# sc.net
KiCad netlist of a schematic drawn in EAGLE
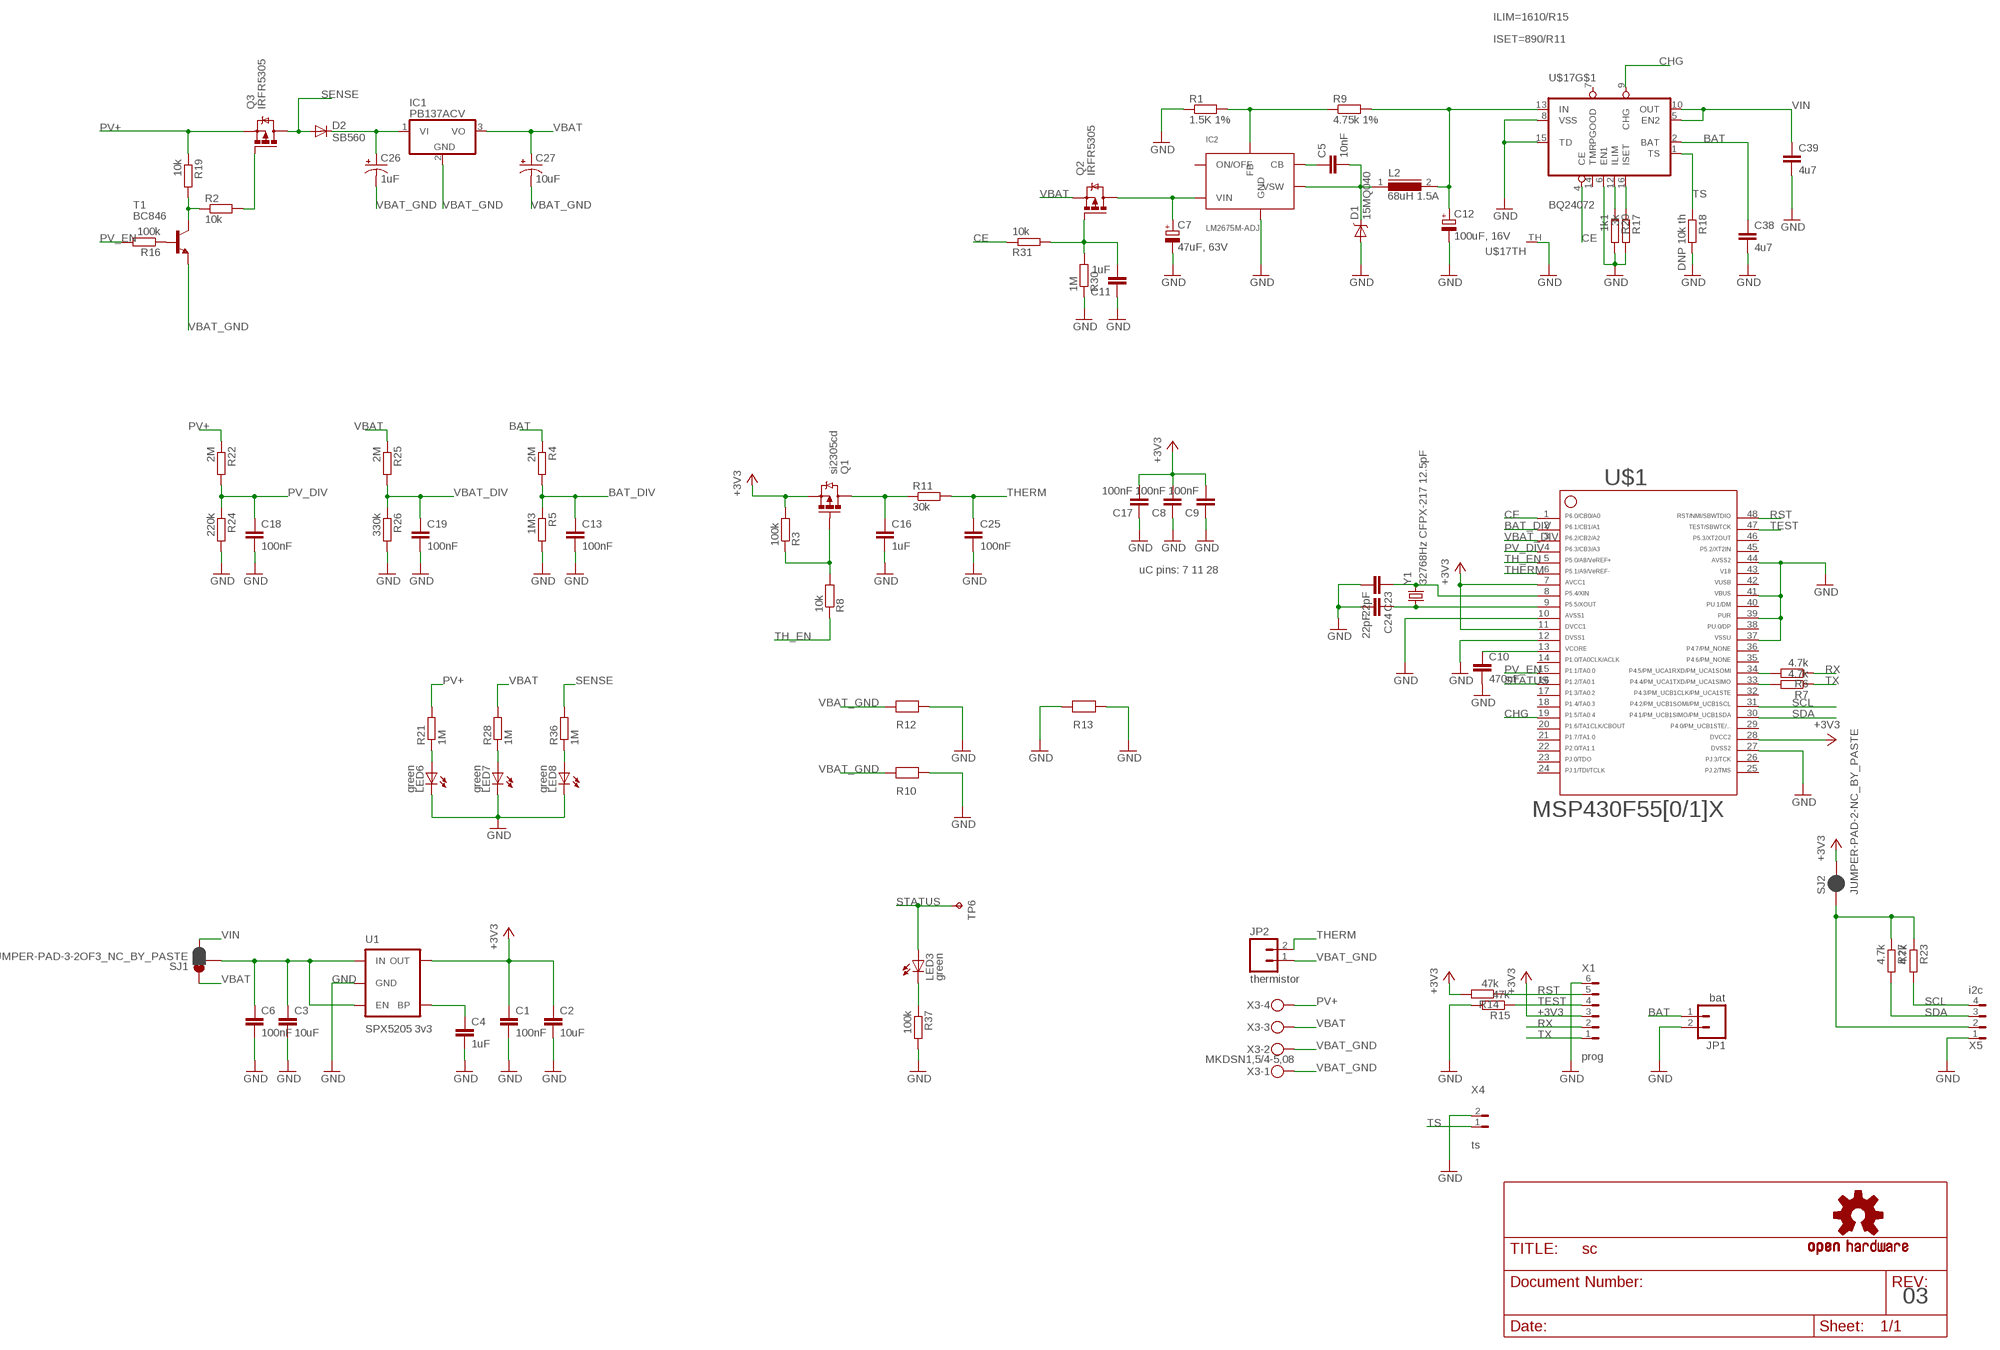
[diagram p0: schematic, sheet 1]

(export (version "E")
  (design (tool "Eeschema 10.0.6"))
  (components
    (comp (ref "C1")
      (value "100nF")
      (footprint "eagle-import:C0805")
      (libsource (lib "eagle-import") (part "C-EUC0805"))
    )
    (comp (ref "C2")
      (value "10uF")
      (footprint "eagle-import:C1206")
      (libsource (lib "eagle-import") (part "C-EUC1206"))
    )
    (comp (ref "C3")
      (value "10uF")
      (footprint "eagle-import:C1206")
      (libsource (lib "eagle-import") (part "C-EUC1206"))
    )
    (comp (ref "C4")
      (value "1uF")
      (footprint "eagle-import:C0805")
      (libsource (lib "eagle-import") (part "C-EUC0805"))
    )
    (comp (ref "C5")
      (value "10nF")
      (footprint "eagle-import:C0805")
      (libsource (lib "eagle-import") (part "C-EUC0805"))
    )
    (comp (ref "C6")
      (value "100nF")
      (footprint "eagle-import:C0805")
      (libsource (lib "eagle-import") (part "C-EUC0805"))
    )
    (comp (ref "C7")
      (value "47uF, 63V")
      (footprint "eagle-import:PANASONIC_F")
      (libsource (lib "eagle-import") (part "CPOL-EUF"))
    )
    (comp (ref "C8")
      (value "100nF")
      (footprint "eagle-import:C0805")
      (libsource (lib "eagle-import") (part "C-EUC0805"))
    )
    (comp (ref "C9")
      (value "100nF")
      (footprint "eagle-import:C0805")
      (libsource (lib "eagle-import") (part "C-EUC0805"))
    )
    (comp (ref "C10")
      (value "470nF")
      (footprint "eagle-import:C0805")
      (libsource (lib "eagle-import") (part "C-EUC0805"))
    )
    (comp (ref "C11")
      (value "1uF")
      (footprint "eagle-import:C0805")
      (libsource (lib "eagle-import") (part "C-EUC0805"))
    )
    (comp (ref "C12")
      (value "100uF, 16V")
      (footprint "eagle-import:PANASONIC_D")
      (libsource (lib "eagle-import") (part "CPOL-EUD"))
    )
    (comp (ref "C13")
      (value "100nF")
      (footprint "eagle-import:C0805")
      (libsource (lib "eagle-import") (part "C-EUC0805"))
    )
    (comp (ref "C16")
      (value "1uF")
      (footprint "eagle-import:C0805")
      (libsource (lib "eagle-import") (part "C-EUC0805"))
    )
    (comp (ref "C17")
      (value "100nF")
      (footprint "eagle-import:C0805")
      (libsource (lib "eagle-import") (part "C-EUC0805"))
    )
    (comp (ref "C18")
      (value "100nF")
      (footprint "eagle-import:C0805")
      (libsource (lib "eagle-import") (part "C-EUC0805"))
    )
    (comp (ref "C19")
      (value "100nF")
      (footprint "eagle-import:C0805")
      (libsource (lib "eagle-import") (part "C-EUC0805"))
    )
    (comp (ref "C23")
      (value "22pF")
      (footprint "eagle-import:C0805")
      (libsource (lib "eagle-import") (part "C-EUC0805"))
    )
    (comp (ref "C24")
      (value "22pF")
      (footprint "eagle-import:C0805")
      (libsource (lib "eagle-import") (part "C-EUC0805"))
    )
    (comp (ref "C25")
      (value "100nF")
      (footprint "eagle-import:C0805")
      (libsource (lib "eagle-import") (part "C-EUC0805"))
    )
    (comp (ref "C26")
      (value "1uF")
      (footprint "eagle-import:PANASONIC_D")
      (libsource (lib "eagle-import") (part "CAP_POLD"))
    )
    (comp (ref "C27")
      (value "10uF")
      (footprint "eagle-import:PANASONIC_D")
      (libsource (lib "eagle-import") (part "CAP_POLD"))
    )
    (comp (ref "C38")
      (value "4u7")
      (footprint "eagle-import:C1206")
      (libsource (lib "eagle-import") (part "C-EUC1206"))
    )
    (comp (ref "C39")
      (value "4u7")
      (footprint "eagle-import:C1206")
      (libsource (lib "eagle-import") (part "C-EUC1206"))
    )
    (comp (ref "D1")
      (value "15MQ040")
      (footprint "eagle-import:SMA-DIODE")
      (libsource (lib "eagle-import") (part "DIODE-SCHOTTKY-MBRA140"))
    )
    (comp (ref "D2")
      (value "SB560")
      (footprint "eagle-import:C1702-05")
      (libsource (lib "eagle-import") (part "DIODE-C1702-05"))
    )
    (comp (ref "IC1")
      (value "PB137ACV")
      (footprint "eagle-import:TO220V")
      (libsource (lib "eagle-import") (part "78TV12"))
    )
    (comp (ref "IC2")
      (value "LM2675M-ADJ")
      (footprint "eagle-import:SO-08")
      (libsource (lib "eagle-import") (part "LM2674"))
    )
    (comp (ref "JP1")
      (value "bat")
      (footprint "eagle-import:1X02")
      (libsource (lib "eagle-import") (part "M02PTH"))
    )
    (comp (ref "JP2")
      (value "thermistor")
      (footprint "eagle-import:1X02")
      (libsource (lib "eagle-import") (part "M02PTH"))
    )
    (comp (ref "L2")
      (value "68uH 1.5A")
      (footprint "eagle-import:DR125")
      (libsource (lib "eagle-import") (part "DR125"))
    )
    (comp (ref "LED3")
      (value "green")
      (footprint "eagle-import:CHIPLED_0805")
      (libsource (lib "eagle-import") (part "LEDCHIPLED_0805"))
    )
    (comp (ref "LED6")
      (value "green")
      (footprint "eagle-import:CHIP-LED0805")
      (libsource (lib "eagle-import") (part "LEDCHIP-LED0805"))
    )
    (comp (ref "LED7")
      (value "green")
      (footprint "eagle-import:CHIP-LED0805")
      (libsource (lib "eagle-import") (part "LEDCHIP-LED0805"))
    )
    (comp (ref "LED8")
      (value "green")
      (footprint "eagle-import:CHIP-LED0805")
      (libsource (lib "eagle-import") (part "LEDCHIP-LED0805"))
    )
    (comp (ref "Q1")
      (value "si2305cd")
      (footprint "eagle-import:SOT23-3_POWER@1")
      (libsource (lib "eagle-import") (part "MOSFET-PCHANNELSMD_POWER"))
    )
    (comp (ref "Q2")
      (value "IRFR5305")
      (footprint "eagle-import:D-PAK_TO252AA")
      (libsource (lib "eagle-import") (part "IRF?5305R"))
    )
    (comp (ref "Q3")
      (value "IRFR5305")
      (footprint "eagle-import:D-PAK_TO252AA")
      (libsource (lib "eagle-import") (part "IRF?5305R"))
    )
    (comp (ref "R1")
      (value "1.5K 1%")
      (footprint "eagle-import:R0805W")
      (libsource (lib "eagle-import") (part "R-EU_R0805W"))
    )
    (comp (ref "R2")
      (value "10k")
      (footprint "eagle-import:R0805W")
      (libsource (lib "eagle-import") (part "R-EU_R0805W"))
    )
    (comp (ref "R3")
      (value "100k")
      (footprint "eagle-import:R0805W")
      (libsource (lib "eagle-import") (part "R-EU_R0805W"))
    )
    (comp (ref "R4")
      (value "2M")
      (footprint "eagle-import:R0805W")
      (libsource (lib "eagle-import") (part "R-EU_R0805W"))
    )
    (comp (ref "R5")
      (value "1M3")
      (footprint "eagle-import:R0805W")
      (libsource (lib "eagle-import") (part "R-EU_R0805W"))
    )
    (comp (ref "R6")
      (value "4.7k")
      (footprint "eagle-import:R0805W")
      (libsource (lib "eagle-import") (part "R-EU_R0805W"))
    )
    (comp (ref "R7")
      (value "4.7k")
      (footprint "eagle-import:R0805W")
      (libsource (lib "eagle-import") (part "R-EU_R0805W"))
    )
    (comp (ref "R8")
      (value "10k")
      (footprint "eagle-import:R0805W")
      (libsource (lib "eagle-import") (part "R-EU_R0805W"))
    )
    (comp (ref "R9")
      (value "4.75k 1%")
      (footprint "eagle-import:R0805W")
      (libsource (lib "eagle-import") (part "R-EU_R0805W"))
    )
    (comp (ref "R10")
      (value "0R_0805")
      (footprint "eagle-import:R0805W")
      (libsource (lib "eagle-import") (part "0R_0805"))
    )
    (comp (ref "R11")
      (value "30k")
      (footprint "eagle-import:R0805W")
      (libsource (lib "eagle-import") (part "R-EU_R0805W"))
    )
    (comp (ref "R12")
      (value "0R_0805")
      (footprint "eagle-import:R0805W")
      (libsource (lib "eagle-import") (part "0R_0805"))
    )
    (comp (ref "R13")
      (value "0R_0805")
      (footprint "eagle-import:R0805W")
      (libsource (lib "eagle-import") (part "0R_0805"))
    )
    (comp (ref "R14")
      (value "47k")
      (footprint "eagle-import:R0805W")
      (libsource (lib "eagle-import") (part "R-EU_R0805W"))
    )
    (comp (ref "R15")
      (value "47k")
      (footprint "eagle-import:R0805W")
      (libsource (lib "eagle-import") (part "R-EU_R0805W"))
    )
    (comp (ref "R16")
      (value "100k")
      (footprint "eagle-import:R0805W")
      (libsource (lib "eagle-import") (part "R-EU_R0805W"))
    )
    (comp (ref "R17")
      (value "3k")
      (footprint "eagle-import:R0805W")
      (libsource (lib "eagle-import") (part "R-EU_R0805W"))
    )
    (comp (ref "R18")
      (value "DNP 10k th")
      (footprint "eagle-import:R0805W")
      (libsource (lib "eagle-import") (part "R-EU_R0805W"))
    )
    (comp (ref "R19")
      (value "10k")
      (footprint "eagle-import:R0805W")
      (libsource (lib "eagle-import") (part "R-EU_R0805W"))
    )
    (comp (ref "R20")
      (value "1k1")
      (footprint "eagle-import:R0805W")
      (libsource (lib "eagle-import") (part "R-EU_R0805W"))
    )
    (comp (ref "R21")
      (value "1M")
      (footprint "eagle-import:R0805W")
      (libsource (lib "eagle-import") (part "R-EU_R0805W"))
    )
    (comp (ref "R22")
      (value "2M")
      (footprint "eagle-import:R0805W")
      (libsource (lib "eagle-import") (part "R-EU_R0805W"))
    )
    (comp (ref "R23")
      (value "4.7k")
      (footprint "eagle-import:R0805W")
      (libsource (lib "eagle-import") (part "R-EU_R0805W"))
    )
    (comp (ref "R24")
      (value "220k")
      (footprint "eagle-import:R0805W")
      (libsource (lib "eagle-import") (part "R-EU_R0805W"))
    )
    (comp (ref "R25")
      (value "2M")
      (footprint "eagle-import:R0805W")
      (libsource (lib "eagle-import") (part "R-EU_R0805W"))
    )
    (comp (ref "R26")
      (value "330k")
      (footprint "eagle-import:R0805W")
      (libsource (lib "eagle-import") (part "R-EU_R0805W"))
    )
    (comp (ref "R27")
      (value "4.7k")
      (footprint "eagle-import:R0805W")
      (libsource (lib "eagle-import") (part "R-EU_R0805W"))
    )
    (comp (ref "R28")
      (value "1M")
      (footprint "eagle-import:R0805W")
      (libsource (lib "eagle-import") (part "R-EU_R0805W"))
    )
    (comp (ref "R30")
      (value "1M")
      (footprint "eagle-import:R0805W")
      (libsource (lib "eagle-import") (part "R-EU_R0805W"))
    )
    (comp (ref "R31")
      (value "10k")
      (footprint "eagle-import:R0805W")
      (libsource (lib "eagle-import") (part "R-EU_R0805W"))
    )
    (comp (ref "R36")
      (value "1M")
      (footprint "eagle-import:R0805W")
      (libsource (lib "eagle-import") (part "R-EU_R0805W"))
    )
    (comp (ref "R37")
      (value "100k")
      (footprint "eagle-import:R0805W")
      (libsource (lib "eagle-import") (part "R-EU_R0805W"))
    )
    (comp (ref "SJ1")
      (value "JUMPER-PAD-3-2OF3_NC_BY_PASTE")
      (footprint "eagle-import:PAD-JUMPER-3-2OF3_NC_BY_PASTE_YES_SILK_FULL_BOX")
      (libsource (lib "eagle-import") (part "JUMPER-PAD-3-2OF3_NC_BY_PASTE"))
    )
    (comp (ref "SJ2")
      (value "JUMPER-PAD-2-NC_BY_PASTE")
      (footprint "eagle-import:PAD-JUMPER-2-NC_BY_PASTE_YES_SILK")
      (libsource (lib "eagle-import") (part "JUMPER-PAD-2-NC_BY_PASTE"))
    )
    (comp (ref "T1")
      (value "BC846")
      (footprint "eagle-import:SOT23")
      (libsource (lib "eagle-import") (part "BC846"))
    )
    (comp (ref "TP6")
      (value "TPTP12R")
      (footprint "eagle-import:TP12R")
      (libsource (lib "eagle-import") (part "TPTP12R"))
    )
    (comp (ref "U$1")
      (value "F55[0/1]X---PT48")
      (footprint "eagle-import:PT48")
      (libsource (lib "eagle-import") (part "F55[0/1]X---PT48"))
    )
    (comp (ref "U$7")
      (value "OSHW-LOGOM")
      (footprint "eagle-import:OSHW-LOGO-M")
      (libsource (lib "eagle-import") (part "OSHW-LOGOM"))
    )
    (comp (ref "U$17")
      (value "BQ24072")
      (footprint "eagle-import:S-PVQFN-N16")
      (libsource (lib "eagle-import") (part "BQ24072"))
    )
    (comp (ref "U1")
      (value "SPX5205 3v3")
      (footprint "eagle-import:SOT23-5")
      (libsource (lib "eagle-import") (part "V_REG_LDOSMD"))
    )
    (comp (ref "X1")
      (value "prog")
      (footprint "eagle-import:0530480610")
      (libsource (lib "eagle-import") (part "MOLEX_6HORIZONTAL"))
    )
    (comp (ref "X3")
      (value "MKDSN1,5/4-5,08")
      (footprint "eagle-import:MKDSN1,5_4-5,08")
      (fields (field (name "MPN") "SMKDSN1,5/4-5,08"))
      (libsource (lib "eagle-import") (part "MKDSN1,5/4-5,08"))
    )
    (comp (ref "X4")
      (value "ts")
      (footprint "eagle-import:0530480210")
      (libsource (lib "eagle-import") (part "MOLEX_2HORIZONTAL"))
    )
    (comp (ref "X5")
      (value "i2c")
      (footprint "eagle-import:0530480401")
      (libsource (lib "eagle-import") (part "MOLEX_4HORIZONTAL"))
    )
    (comp (ref "Y1")
      (value "32768Hz CFPX-217 12.5pF")
      (footprint "eagle-import:CRYSTAL-SMD-3.2X1.5")
      (libsource (lib "eagle-import") (part "CRYSTAL3.2X1.5"))
    )
  )
  (nets
    (net (code "1") (name "+3V3") (class "Default")
      (node (ref "C1") (pin "1") (pinfunction "1_1") (pintype "passive"))
      (node (ref "C17") (pin "2") (pinfunction "2_2") (pintype "passive"))
      (node (ref "C2") (pin "1") (pinfunction "1_1") (pintype "passive"))
      (node (ref "C8") (pin "2") (pinfunction "2_2") (pintype "passive"))
      (node (ref "C9") (pin "2") (pinfunction "2_2") (pintype "passive"))
      (node (ref "Q1") (pin "2") (pinfunction "S_2") (pintype "passive"))
      (node (ref "R14") (pin "2") (pinfunction "2_2") (pintype "passive"))
      (node (ref "R3") (pin "2") (pinfunction "2_2") (pintype "passive"))
      (node (ref "SJ2") (pin "2") (pinfunction "2_2") (pintype "passive"))
      (node (ref "U$1") (pin "11") (pinfunction "11_11") (pintype "power_in"))
      (node (ref "U$1") (pin "28") (pinfunction "28_28") (pintype "power_in"))
      (node (ref "U$1") (pin "7") (pinfunction "7_7") (pintype "power_in"))
      (node (ref "U1") (pin "5") (pinfunction "OUT_5") (pintype "passive"))
      (node (ref "X1") (pin "3") (pinfunction "4_3") (pintype "passive"))
    )
    (net (code "2") (name "/42") (class "Default")
      (node (ref "U$1") (pin "42") (pinfunction "42_42") (pintype "power_in"))
    )
    (net (code "3") (name "/43") (class "Default")
      (node (ref "U$1") (pin "43") (pinfunction "43_43") (pintype "power_in"))
    )
    (net (code "4") (name "/46") (class "Default")
      (node (ref "U$1") (pin "46") (pinfunction "46_46") (pintype "power_in"))
    )
    (net (code "5") (name "/BAT") (class "Default")
      (node (ref "C38") (pin "1") (pinfunction "1_1") (pintype "passive"))
      (node (ref "JP1") (pin "1") (pinfunction "1_1") (pintype "passive"))
      (node (ref "R4") (pin "1") (pinfunction "1_1") (pintype "passive"))
      (node (ref "U$17") (pin "2") (pinfunction "BAT_2") (pintype "input"))
    )
    (net (code "6") (name "/BAT_DIV") (class "Default")
      (node (ref "C13") (pin "1") (pinfunction "1_1") (pintype "passive"))
      (node (ref "R4") (pin "2") (pinfunction "2_2") (pintype "passive"))
      (node (ref "R5") (pin "1") (pinfunction "1_1") (pintype "passive"))
      (node (ref "U$1") (pin "2") (pinfunction "2_2") (pintype "bidirectional"))
    )
    (net (code "7") (name "/CE") (class "Default")
      (node (ref "R31") (pin "1") (pinfunction "1_1") (pintype "passive"))
      (node (ref "U$1") (pin "1") (pinfunction "1_1") (pintype "bidirectional"))
      (node (ref "U$17") (pin "4") (pinfunction "CE_4") (pintype "bidirectional"))
    )
    (net (code "8") (name "/CHG") (class "Default")
      (node (ref "U$1") (pin "19") (pinfunction "19_19") (pintype "bidirectional"))
      (node (ref "U$17") (pin "9") (pinfunction "CHG_9") (pintype "bidirectional"))
    )
    (net (code "9") (name "/PV+") (class "Default")
      (node (ref "Q3") (pin "3") (pinfunction "S_3") (pintype "passive"))
      (node (ref "R19") (pin "1") (pinfunction "1_1") (pintype "passive"))
      (node (ref "R21") (pin "2") (pinfunction "2_2") (pintype "passive"))
      (node (ref "R22") (pin "1") (pinfunction "1_1") (pintype "passive"))
      (node (ref "X3") (pin "4") (pinfunction "KL_4") (pintype "passive"))
    )
    (net (code "10") (name "/PV_DIV") (class "Default")
      (node (ref "C18") (pin "1") (pinfunction "1_1") (pintype "passive"))
      (node (ref "R22") (pin "2") (pinfunction "2_2") (pintype "passive"))
      (node (ref "R24") (pin "1") (pinfunction "1_1") (pintype "passive"))
      (node (ref "U$1") (pin "4") (pinfunction "4_4") (pintype "bidirectional"))
    )
    (net (code "11") (name "/PV_EN") (class "Default")
      (node (ref "R16") (pin "2") (pinfunction "2_2") (pintype "passive"))
      (node (ref "U$1") (pin "15") (pinfunction "15_15") (pintype "bidirectional"))
    )
    (net (code "12") (name "/RST") (class "Default")
      (node (ref "R14") (pin "1") (pinfunction "1_1") (pintype "passive"))
      (node (ref "U$1") (pin "48") (pinfunction "48_48") (pintype "bidirectional"))
      (node (ref "X1") (pin "5") (pinfunction "2_5") (pintype "passive"))
    )
    (net (code "13") (name "/RX") (class "Default")
      (node (ref "R6") (pin "1") (pinfunction "1_1") (pintype "passive"))
      (node (ref "X1") (pin "2") (pinfunction "5_2") (pintype "passive"))
    )
    (net (code "14") (name "/SCL") (class "Default")
      (node (ref "R23") (pin "2") (pinfunction "2_2") (pintype "passive"))
      (node (ref "U$1") (pin "31") (pinfunction "31_31") (pintype "bidirectional"))
      (node (ref "X5") (pin "4") (pinfunction "1_4") (pintype "passive"))
    )
    (net (code "15") (name "/SDA") (class "Default")
      (node (ref "R27") (pin "2") (pinfunction "2_2") (pintype "passive"))
      (node (ref "U$1") (pin "30") (pinfunction "30_30") (pintype "bidirectional"))
      (node (ref "X5") (pin "3") (pinfunction "2_3") (pintype "passive"))
    )
    (net (code "16") (name "/SENSE") (class "Default")
      (node (ref "D2") (pin "A") (pinfunction "A_A") (pintype "passive"))
      (node (ref "Q3") (pin "4") (pinfunction "D_4") (pintype "passive"))
      (node (ref "R36") (pin "2") (pinfunction "2_2") (pintype "passive"))
    )
    (net (code "17") (name "/STATUS") (class "Default")
      (node (ref "LED3") (pin "A") (pinfunction "A_A") (pintype "passive"))
      (node (ref "TP6") (pin "TP") (pinfunction "TP_TP") (pintype "input"))
      (node (ref "U$1") (pin "16") (pinfunction "16_16") (pintype "bidirectional"))
    )
    (net (code "18") (name "/TEST") (class "Default")
      (node (ref "R15") (pin "1") (pinfunction "1_1") (pintype "passive"))
      (node (ref "U$1") (pin "47") (pinfunction "47_47") (pintype "input"))
      (node (ref "X1") (pin "4") (pinfunction "3_4") (pintype "passive"))
    )
    (net (code "19") (name "/THERM") (class "Default")
      (node (ref "C25") (pin "1") (pinfunction "1_1") (pintype "passive"))
      (node (ref "JP2") (pin "2") (pinfunction "2_2") (pintype "passive"))
      (node (ref "R11") (pin "2") (pinfunction "2_2") (pintype "passive"))
      (node (ref "U$1") (pin "6") (pinfunction "6_6") (pintype "bidirectional"))
    )
    (net (code "20") (name "/TH_EN") (class "Default")
      (node (ref "R8") (pin "1") (pinfunction "1_1") (pintype "passive"))
      (node (ref "U$1") (pin "5") (pinfunction "5_5") (pintype "bidirectional"))
    )
    (net (code "21") (name "/TS") (class "Default")
      (node (ref "R18") (pin "1") (pinfunction "1_1") (pintype "passive"))
      (node (ref "U$17") (pin "1") (pinfunction "TS_1") (pintype "input"))
      (node (ref "X4") (pin "1") (pinfunction "2_1") (pintype "passive"))
    )
    (net (code "22") (name "/TX") (class "Default")
      (node (ref "R7") (pin "1") (pinfunction "1_1") (pintype "passive"))
      (node (ref "X1") (pin "1") (pinfunction "6_1") (pintype "passive"))
    )
    (net (code "23") (name "/VBAT") (class "Default")
      (node (ref "C27") (pin "+") (pinfunction "+_+") (pintype "passive"))
      (node (ref "IC1") (pin "3") (pinfunction "VO_3") (pintype "passive"))
      (node (ref "Q2") (pin "3") (pinfunction "S_3") (pintype "passive"))
      (node (ref "R25") (pin "1") (pinfunction "1_1") (pintype "passive"))
      (node (ref "R28") (pin "2") (pinfunction "2_2") (pintype "passive"))
      (node (ref "SJ1") (pin "1") (pinfunction "1_1") (pintype "passive"))
      (node (ref "X3") (pin "3") (pinfunction "KL_3") (pintype "passive"))
    )
    (net (code "24") (name "/VBAT_DIV") (class "Default")
      (node (ref "C19") (pin "1") (pinfunction "1_1") (pintype "passive"))
      (node (ref "R25") (pin "2") (pinfunction "2_2") (pintype "passive"))
      (node (ref "R26") (pin "1") (pinfunction "1_1") (pintype "passive"))
      (node (ref "U$1") (pin "3") (pinfunction "3_3") (pintype "bidirectional"))
    )
    (net (code "25") (name "/VBAT_GND") (class "Default")
      (node (ref "C26") (pin "-") (pinfunction "-_-") (pintype "passive"))
      (node (ref "C27") (pin "-") (pinfunction "-_-") (pintype "passive"))
      (node (ref "IC1") (pin "2") (pinfunction "GND_2") (pintype "passive"))
      (node (ref "JP2") (pin "1") (pinfunction "1_1") (pintype "passive"))
      (node (ref "R10") (pin "1") (pinfunction "P$1_1") (pintype "bidirectional"))
      (node (ref "R12") (pin "1") (pinfunction "P$1_1") (pintype "bidirectional"))
      (node (ref "T1") (pin "2") (pinfunction "E_2") (pintype "passive"))
      (node (ref "X3") (pin "1") (pinfunction "KL_1") (pintype "passive"))
      (node (ref "X3") (pin "2") (pinfunction "KL_2") (pintype "passive"))
    )
    (net (code "26") (name "/VIN") (class "Default")
      (node (ref "C39") (pin "1") (pinfunction "1_1") (pintype "passive"))
      (node (ref "SJ1") (pin "3") (pinfunction "3_3") (pintype "passive"))
      (node (ref "U$17") (pin "10") (pinfunction "OUT_10") (pintype "output"))
      (node (ref "U$17") (pin "5") (pinfunction "EN2_5") (pintype "input"))
    )
    (net (code "27") (name "GND") (class "Default")
      (node (ref "C1") (pin "2") (pinfunction "2_2") (pintype "passive"))
      (node (ref "C10") (pin "2") (pinfunction "2_2") (pintype "passive"))
      (node (ref "C11") (pin "1") (pinfunction "1_1") (pintype "passive"))
      (node (ref "C12") (pin "-") (pinfunction "-_-") (pintype "passive"))
      (node (ref "C13") (pin "2") (pinfunction "2_2") (pintype "passive"))
      (node (ref "C16") (pin "2") (pinfunction "2_2") (pintype "passive"))
      (node (ref "C17") (pin "1") (pinfunction "1_1") (pintype "passive"))
      (node (ref "C18") (pin "2") (pinfunction "2_2") (pintype "passive"))
      (node (ref "C19") (pin "2") (pinfunction "2_2") (pintype "passive"))
      (node (ref "C2") (pin "2") (pinfunction "2_2") (pintype "passive"))
      (node (ref "C23") (pin "2") (pinfunction "2_2") (pintype "passive"))
      (node (ref "C24") (pin "2") (pinfunction "2_2") (pintype "passive"))
      (node (ref "C25") (pin "2") (pinfunction "2_2") (pintype "passive"))
      (node (ref "C3") (pin "2") (pinfunction "2_2") (pintype "passive"))
      (node (ref "C38") (pin "2") (pinfunction "2_2") (pintype "passive"))
      (node (ref "C39") (pin "2") (pinfunction "2_2") (pintype "passive"))
      (node (ref "C4") (pin "2") (pinfunction "2_2") (pintype "passive"))
      (node (ref "C6") (pin "2") (pinfunction "2_2") (pintype "passive"))
      (node (ref "C7") (pin "-") (pinfunction "-_-") (pintype "passive"))
      (node (ref "C8") (pin "1") (pinfunction "1_1") (pintype "passive"))
      (node (ref "C9") (pin "1") (pinfunction "1_1") (pintype "passive"))
      (node (ref "D1") (pin "A") (pinfunction "A_A") (pintype "passive"))
      (node (ref "IC2") (pin "6") (pinfunction "GND_6") (pintype "bidirectional"))
      (node (ref "JP1") (pin "2") (pinfunction "2_2") (pintype "passive"))
      (node (ref "LED6") (pin "C") (pinfunction "C_C") (pintype "passive"))
      (node (ref "LED7") (pin "C") (pinfunction "C_C") (pintype "passive"))
      (node (ref "LED8") (pin "C") (pinfunction "C_C") (pintype "passive"))
      (node (ref "R1") (pin "1") (pinfunction "1_1") (pintype "passive"))
      (node (ref "R10") (pin "2") (pinfunction "P$2_2") (pintype "bidirectional"))
      (node (ref "R12") (pin "2") (pinfunction "P$2_2") (pintype "bidirectional"))
      (node (ref "R13") (pin "1") (pinfunction "P$1_1") (pintype "bidirectional"))
      (node (ref "R13") (pin "2") (pinfunction "P$2_2") (pintype "bidirectional"))
      (node (ref "R15") (pin "2") (pinfunction "2_2") (pintype "passive"))
      (node (ref "R17") (pin "2") (pinfunction "2_2") (pintype "passive"))
      (node (ref "R18") (pin "2") (pinfunction "2_2") (pintype "passive"))
      (node (ref "R20") (pin "2") (pinfunction "2_2") (pintype "passive"))
      (node (ref "R24") (pin "2") (pinfunction "2_2") (pintype "passive"))
      (node (ref "R26") (pin "2") (pinfunction "2_2") (pintype "passive"))
      (node (ref "R30") (pin "1") (pinfunction "1_1") (pintype "passive"))
      (node (ref "R37") (pin "2") (pinfunction "2_2") (pintype "passive"))
      (node (ref "R5") (pin "2") (pinfunction "2_2") (pintype "passive"))
      (node (ref "U$1") (pin "10") (pinfunction "10_10") (pintype "power_in"))
      (node (ref "U$1") (pin "12") (pinfunction "12_12") (pintype "power_in"))
      (node (ref "U$1") (pin "27") (pinfunction "27_27") (pintype "power_in"))
      (node (ref "U$1") (pin "37") (pinfunction "37_37") (pintype "power_in"))
      (node (ref "U$1") (pin "39") (pinfunction "39_39") (pintype "bidirectional"))
      (node (ref "U$1") (pin "41") (pinfunction "41_41") (pintype "power_in"))
      (node (ref "U$1") (pin "44") (pinfunction "44_44") (pintype "power_in"))
      (node (ref "U$17") (pin "15") (pinfunction "TD_15") (pintype "bidirectional"))
      (node (ref "U$17") (pin "6") (pinfunction "EN1_6") (pintype "bidirectional"))
      (node (ref "U$17") (pin "8") (pinfunction "VSS_8") (pintype "power_in"))
      (node (ref "U$17") (pin "TH") (pinfunction "TH_TH") (pintype "passive"))
      (node (ref "U1") (pin "2") (pinfunction "GND_2") (pintype "input"))
      (node (ref "X1") (pin "6") (pinfunction "1_6") (pintype "passive"))
      (node (ref "X4") (pin "2") (pinfunction "1_2") (pintype "passive"))
      (node (ref "X5") (pin "1") (pinfunction "4_1") (pintype "passive"))
    )
    (net (code "28") (name "Net-(C10-Pad1)") (class "Default")
      (node (ref "C10") (pin "1") (pinfunction "1_1") (pintype "passive"))
      (node (ref "U$1") (pin "13") (pinfunction "13_13") (pintype "power_in"))
    )
    (net (code "29") (name "Net-(IC1-VI)") (class "Default")
      (node (ref "C26") (pin "+") (pinfunction "+_+") (pintype "passive"))
      (node (ref "D2") (pin "C") (pinfunction "C_C") (pintype "passive"))
      (node (ref "IC1") (pin "1") (pinfunction "VI_1") (pintype "input"))
    )
    (net (code "30") (name "Net-(IC2-CB)") (class "Default")
      (node (ref "C5") (pin "1") (pinfunction "1_1") (pintype "passive"))
      (node (ref "IC2") (pin "1") (pinfunction "CB_1") (pintype "bidirectional"))
    )
    (net (code "31") (name "Net-(IC2-FB)") (class "Default")
      (node (ref "IC2") (pin "4") (pinfunction "FB_4") (pintype "bidirectional"))
      (node (ref "R1") (pin "2") (pinfunction "2_2") (pintype "passive"))
      (node (ref "R9") (pin "1") (pinfunction "1_1") (pintype "passive"))
    )
    (net (code "32") (name "Net-(IC2-VIN)") (class "Default")
      (node (ref "C7") (pin "+") (pinfunction "+_+") (pintype "passive"))
      (node (ref "IC2") (pin "7") (pinfunction "VIN_7") (pintype "bidirectional"))
      (node (ref "Q2") (pin "4") (pinfunction "D_4") (pintype "passive"))
    )
    (net (code "33") (name "Net-(IC2-VSW)") (class "Default")
      (node (ref "C5") (pin "2") (pinfunction "2_2") (pintype "passive"))
      (node (ref "D1") (pin "C") (pinfunction "C_C") (pintype "passive"))
      (node (ref "IC2") (pin "8") (pinfunction "VSW_8") (pintype "bidirectional"))
      (node (ref "L2") (pin "1") (pinfunction "1_1") (pintype "passive"))
    )
    (net (code "34") (name "Net-(LED3-PadC)") (class "Default")
      (node (ref "LED3") (pin "C") (pinfunction "C_C") (pintype "passive"))
      (node (ref "R37") (pin "1") (pinfunction "1_1") (pintype "passive"))
    )
    (net (code "35") (name "Net-(LED6-PadA)") (class "Default")
      (node (ref "LED6") (pin "A") (pinfunction "A_A") (pintype "passive"))
      (node (ref "R21") (pin "1") (pinfunction "1_1") (pintype "passive"))
    )
    (net (code "36") (name "Net-(LED7-PadA)") (class "Default")
      (node (ref "LED7") (pin "A") (pinfunction "A_A") (pintype "passive"))
      (node (ref "R28") (pin "1") (pinfunction "1_1") (pintype "passive"))
    )
    (net (code "37") (name "Net-(LED8-PadA)") (class "Default")
      (node (ref "LED8") (pin "A") (pinfunction "A_A") (pintype "passive"))
      (node (ref "R36") (pin "1") (pinfunction "1_1") (pintype "passive"))
    )
    (net (code "38") (name "Net-(Q1-D)") (class "Default")
      (node (ref "C16") (pin "1") (pinfunction "1_1") (pintype "passive"))
      (node (ref "Q1") (pin "3") (pinfunction "D_3") (pintype "passive"))
      (node (ref "R11") (pin "1") (pinfunction "1_1") (pintype "passive"))
    )
    (net (code "39") (name "Net-(Q1-G)") (class "Default")
      (node (ref "Q1") (pin "1") (pinfunction "G_1") (pintype "passive"))
      (node (ref "R3") (pin "1") (pinfunction "1_1") (pintype "passive"))
      (node (ref "R8") (pin "2") (pinfunction "2_2") (pintype "passive"))
    )
    (net (code "40") (name "Net-(Q2-G)") (class "Default")
      (node (ref "C11") (pin "2") (pinfunction "2_2") (pintype "passive"))
      (node (ref "Q2") (pin "1") (pinfunction "G_1") (pintype "passive"))
      (node (ref "R30") (pin "2") (pinfunction "2_2") (pintype "passive"))
      (node (ref "R31") (pin "2") (pinfunction "2_2") (pintype "passive"))
    )
    (net (code "41") (name "Net-(Q3-G)") (class "Default")
      (node (ref "Q3") (pin "1") (pinfunction "G_1") (pintype "passive"))
      (node (ref "R2") (pin "2") (pinfunction "2_2") (pintype "passive"))
    )
    (net (code "42") (name "Net-(R6-Pad2)") (class "Default")
      (node (ref "R6") (pin "2") (pinfunction "2_2") (pintype "passive"))
      (node (ref "U$1") (pin "34") (pinfunction "34_34") (pintype "bidirectional"))
    )
    (net (code "43") (name "Net-(R7-Pad2)") (class "Default")
      (node (ref "R7") (pin "2") (pinfunction "2_2") (pintype "passive"))
      (node (ref "U$1") (pin "33") (pinfunction "33_33") (pintype "bidirectional"))
    )
    (net (code "44") (name "Net-(T1-B)") (class "Default")
      (node (ref "R16") (pin "1") (pinfunction "1_1") (pintype "passive"))
      (node (ref "T1") (pin "1") (pinfunction "B_1") (pintype "passive"))
    )
    (net (code "45") (name "Net-(T1-C)") (class "Default")
      (node (ref "R19") (pin "2") (pinfunction "2_2") (pintype "passive"))
      (node (ref "R2") (pin "1") (pinfunction "1_1") (pintype "passive"))
      (node (ref "T1") (pin "3") (pinfunction "C_3") (pintype "passive"))
    )
    (net (code "46") (name "Net-(U$17A-ILIM)") (class "Default")
      (node (ref "R20") (pin "1") (pinfunction "1_1") (pintype "passive"))
      (node (ref "U$17") (pin "12") (pinfunction "ILIM_12") (pintype "bidirectional"))
    )
    (net (code "47") (name "Net-(U$17A-IN)") (class "Default")
      (node (ref "C12") (pin "+") (pinfunction "+_+") (pintype "passive"))
      (node (ref "L2") (pin "2") (pinfunction "2_2") (pintype "passive"))
      (node (ref "R9") (pin "2") (pinfunction "2_2") (pintype "passive"))
      (node (ref "U$17") (pin "13") (pinfunction "IN_13") (pintype "input"))
    )
    (net (code "48") (name "Net-(U$17A-ISET)") (class "Default")
      (node (ref "R17") (pin "1") (pinfunction "1_1") (pintype "passive"))
      (node (ref "U$17") (pin "16") (pinfunction "ISET_16") (pintype "input"))
    )
    (net (code "49") (name "Net-(U1-BP)") (class "Default")
      (node (ref "C4") (pin "1") (pinfunction "1_1") (pintype "passive"))
      (node (ref "U1") (pin "4") (pinfunction "BP_4") (pintype "input"))
    )
    (net (code "50") (name "Net-(U1-EN)") (class "Default")
      (node (ref "C3") (pin "1") (pinfunction "1_1") (pintype "passive"))
      (node (ref "C6") (pin "1") (pinfunction "1_1") (pintype "passive"))
      (node (ref "SJ1") (pin "2") (pinfunction "2_2") (pintype "passive"))
      (node (ref "U1") (pin "1") (pinfunction "IN_1") (pintype "input"))
      (node (ref "U1") (pin "3") (pinfunction "EN_3") (pintype "input"))
    )
    (net (code "51") (name "Net-(X5-3)") (class "Default")
      (node (ref "R23") (pin "1") (pinfunction "1_1") (pintype "passive"))
      (node (ref "R27") (pin "1") (pinfunction "1_1") (pintype "passive"))
      (node (ref "SJ2") (pin "1") (pinfunction "1_1") (pintype "passive"))
      (node (ref "X5") (pin "2") (pinfunction "3_2") (pintype "passive"))
    )
    (net (code "52") (name "Net-(Y1-1)") (class "Default")
      (node (ref "C24") (pin "1") (pinfunction "1_1") (pintype "passive"))
      (node (ref "U$1") (pin "9") (pinfunction "9_9") (pintype "bidirectional"))
      (node (ref "Y1") (pin "P$1") (pinfunction "1_P$1") (pintype "passive"))
    )
    (net (code "53") (name "Net-(Y1-2)") (class "Default")
      (node (ref "C23") (pin "1") (pinfunction "1_1") (pintype "passive"))
      (node (ref "U$1") (pin "8") (pinfunction "8_8") (pintype "bidirectional"))
      (node (ref "Y1") (pin "P$2") (pinfunction "2_P$2") (pintype "passive"))
    )
    (net (code "54") (name "unconnected-(IC2-ON{slash}OFF-Pad5)") (class "Default")
      (node (ref "IC2") (pin "5") (pinfunction "ON/OFF_5") (pintype "bidirectional"))
    )
    (net (code "55") (name "unconnected-(U$1-Pad14)") (class "Default")
      (node (ref "U$1") (pin "14") (pinfunction "14_14") (pintype "bidirectional"))
    )
    (net (code "56") (name "unconnected-(U$1-Pad17)") (class "Default")
      (node (ref "U$1") (pin "17") (pinfunction "17_17") (pintype "bidirectional"))
    )
    (net (code "57") (name "unconnected-(U$1-Pad18)") (class "Default")
      (node (ref "U$1") (pin "18") (pinfunction "18_18") (pintype "bidirectional"))
    )
    (net (code "58") (name "unconnected-(U$1-Pad20)") (class "Default")
      (node (ref "U$1") (pin "20") (pinfunction "20_20") (pintype "bidirectional"))
    )
    (net (code "59") (name "unconnected-(U$1-Pad21)") (class "Default")
      (node (ref "U$1") (pin "21") (pinfunction "21_21") (pintype "bidirectional"))
    )
    (net (code "60") (name "unconnected-(U$1-Pad22)") (class "Default")
      (node (ref "U$1") (pin "22") (pinfunction "22_22") (pintype "bidirectional"))
    )
    (net (code "61") (name "unconnected-(U$1-Pad23)") (class "Default")
      (node (ref "U$1") (pin "23") (pinfunction "23_23") (pintype "bidirectional"))
    )
    (net (code "62") (name "unconnected-(U$1-Pad24)") (class "Default")
      (node (ref "U$1") (pin "24") (pinfunction "24_24") (pintype "bidirectional"))
    )
    (net (code "63") (name "unconnected-(U$1-Pad25)") (class "Default")
      (node (ref "U$1") (pin "25") (pinfunction "25_25") (pintype "bidirectional"))
    )
    (net (code "64") (name "unconnected-(U$1-Pad26)") (class "Default")
      (node (ref "U$1") (pin "26") (pinfunction "26_26") (pintype "bidirectional"))
    )
    (net (code "65") (name "unconnected-(U$1-Pad29)") (class "Default")
      (node (ref "U$1") (pin "29") (pinfunction "29_29") (pintype "bidirectional"))
    )
    (net (code "66") (name "unconnected-(U$1-Pad32)") (class "Default")
      (node (ref "U$1") (pin "32") (pinfunction "32_32") (pintype "bidirectional"))
    )
    (net (code "67") (name "unconnected-(U$1-Pad35)") (class "Default")
      (node (ref "U$1") (pin "35") (pinfunction "35_35") (pintype "bidirectional"))
    )
    (net (code "68") (name "unconnected-(U$1-Pad36)") (class "Default")
      (node (ref "U$1") (pin "36") (pinfunction "36_36") (pintype "bidirectional"))
    )
    (net (code "69") (name "unconnected-(U$1-Pad38)") (class "Default")
      (node (ref "U$1") (pin "38") (pinfunction "38_38") (pintype "bidirectional"))
    )
    (net (code "70") (name "unconnected-(U$1-Pad40)") (class "Default")
      (node (ref "U$1") (pin "40") (pinfunction "40_40") (pintype "bidirectional"))
    )
    (net (code "71") (name "unconnected-(U$1-Pad45)") (class "Default")
      (node (ref "U$1") (pin "45") (pinfunction "45_45") (pintype "bidirectional"))
    )
    (net (code "72") (name "unconnected-(U$17A-PGOOD-Pad7)") (class "Default")
      (node (ref "U$17") (pin "7") (pinfunction "PGOOD_7") (pintype "bidirectional"))
    )
    (net (code "73") (name "unconnected-(U$17A-TMR-Pad14)") (class "Default")
      (node (ref "U$17") (pin "14") (pinfunction "TMR_14") (pintype "bidirectional"))
    )
  )
)
